# OLED.net
KiCad netlist of a schematic drawn in Altium Designer
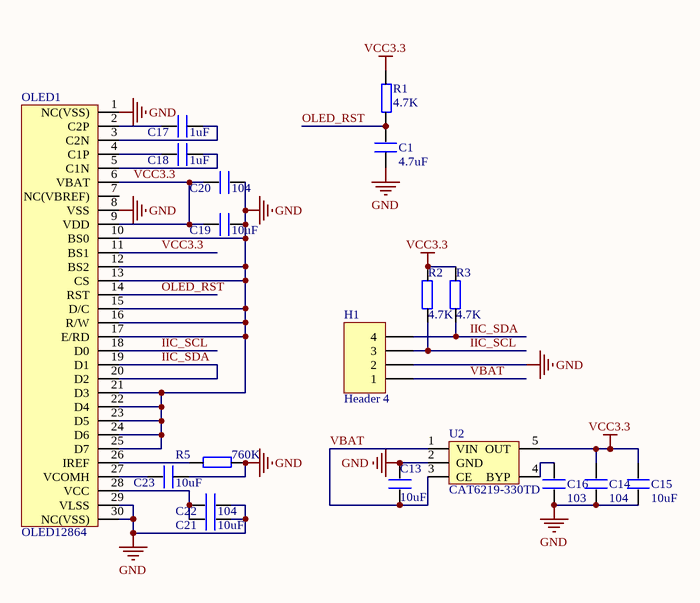
[diagram p0: OLED.SchDoc]

(export (version "E")
  (design (tool "Eeschema 10.0.6"))
  (components
    (comp (ref "C1")
      (value "4.7uF")
      (footprint "C 0603_M")
      (libsource (lib "WarShip V3 STM32103封装库") (part "C"))
    )
    (comp (ref "C13")
      (value "10uF")
      (footprint "C 0603_M")
      (libsource (lib "WarShip V3 STM32103封装库") (part "C"))
    )
    (comp (ref "C14")
      (value "104")
      (footprint "C 0603_M")
      (libsource (lib "WarShip V3 STM32103封装库") (part "C"))
    )
    (comp (ref "C15")
      (value "10uF")
      (footprint "C 0603_M")
      (libsource (lib "WarShip V3 STM32103封装库") (part "C"))
    )
    (comp (ref "C16")
      (value "103")
      (footprint "C 0603_M")
      (libsource (lib "WarShip V3 STM32103封装库") (part "C"))
    )
    (comp (ref "C17")
      (value "1uF")
      (footprint "C 0603_M")
      (libsource (lib "WarShip V3 STM32103封装库") (part "C"))
    )
    (comp (ref "C18")
      (value "1uF")
      (footprint "C 0603_M")
      (libsource (lib "WarShip V3 STM32103封装库") (part "C"))
    )
    (comp (ref "C19")
      (value "10uF")
      (footprint "C 0603_M")
      (libsource (lib "WarShip V3 STM32103封装库") (part "C"))
    )
    (comp (ref "C20")
      (value "104")
      (footprint "C 0603_M")
      (libsource (lib "WarShip V3 STM32103封装库") (part "C"))
    )
    (comp (ref "C21")
      (value "10uF")
      (footprint "C 0603_M")
      (libsource (lib "WarShip V3 STM32103封装库") (part "C"))
    )
    (comp (ref "C22")
      (value "104")
      (footprint "C 0603_M")
      (libsource (lib "WarShip V3 STM32103封装库") (part "C"))
    )
    (comp (ref "C23")
      (value "10uF")
      (footprint "C 0603_M")
      (libsource (lib "WarShip V3 STM32103封装库") (part "C"))
    )
    (comp (ref "H1")
      (value "Header 4")
      (footprint "HDR2.54-LI-4P")
      (description "Header, 4-Pin")
      (fields (field (name "PUBLISHER") "Altium Limited"))
      (libsource (lib "WarShip V3 STM32103封装库") (part "Header 4"))
    )
    (comp (ref "OLED1")
      (value "OLED12864")
      (footprint "OLED_0.96")
      (libsource (lib "OLED模块封装库") (part "OLED12864"))
    )
    (comp (ref "R1")
      (value "4.7K")
      (footprint "R 0603_M")
      (libsource (lib "WarShip V3 STM32103封装库") (part "R"))
    )
    (comp (ref "R2")
      (value "4.7K")
      (footprint "R 0603_M")
      (libsource (lib "WarShip V3 STM32103封装库") (part "R"))
    )
    (comp (ref "R3")
      (value "4.7K")
      (footprint "R 0603_M")
      (libsource (lib "WarShip V3 STM32103封装库") (part "R"))
    )
    (comp (ref "R5")
      (value "760K")
      (footprint "R 0603_M")
      (libsource (lib "WarShip V3 STM32103封装库") (part "R"))
    )
    (comp (ref "U2")
      (value "CAT6219-330TD")
      (footprint "SOT-23-5")
      (description "3.3V 500mA LDO")
      (libsource (lib "STM32H743核心板封装库") (part "CAT6219-330TD"))
    )
  )
  (nets
    (net (code "1") (name "/IIC_SCL") (class "Default")
      (node (ref "H1") (pin "3") (pinfunction "3_3") (pintype "passive"))
      (node (ref "OLED1") (pin "18") (pinfunction "D0_18") (pintype "passive"))
      (node (ref "R2") (pin "2") (pintype "passive"))
    )
    (net (code "2") (name "/IIC_SDA") (class "Default")
      (node (ref "H1") (pin "4") (pinfunction "4_4") (pintype "passive"))
      (node (ref "OLED1") (pin "19") (pinfunction "D1_19") (pintype "passive"))
      (node (ref "OLED1") (pin "20") (pinfunction "D2_20") (pintype "passive"))
      (node (ref "R3") (pin "2") (pintype "passive"))
    )
    (net (code "3") (name "/OLED_RST") (class "Default")
      (node (ref "C1") (pin "1") (pintype "passive"))
      (node (ref "OLED1") (pin "14") (pinfunction "RST_14") (pintype "passive"))
      (node (ref "R1") (pin "1") (pintype "passive"))
    )
    (net (code "4") (name "/VBAT") (class "Default")
      (node (ref "C13") (pin "1") (pintype "passive"))
      (node (ref "H1") (pin "1") (pinfunction "1_1") (pintype "passive"))
      (node (ref "U2") (pin "1") (pinfunction "VIN_1") (pintype "passive"))
      (node (ref "U2") (pin "3") (pinfunction "CE_3") (pintype "passive"))
    )
    (net (code "5") (name "GND") (class "Default")
      (node (ref "C1") (pin "2") (pintype "passive"))
      (node (ref "C13") (pin "2") (pintype "passive"))
      (node (ref "C14") (pin "1") (pintype "passive"))
      (node (ref "C15") (pin "1") (pintype "passive"))
      (node (ref "C16") (pin "1") (pintype "passive"))
      (node (ref "C19") (pin "1") (pintype "passive"))
      (node (ref "C20") (pin "1") (pintype "passive"))
      (node (ref "C21") (pin "1") (pintype "passive"))
      (node (ref "C22") (pin "1") (pintype "passive"))
      (node (ref "C23") (pin "1") (pintype "passive"))
      (node (ref "H1") (pin "2") (pinfunction "2_2") (pintype "passive"))
      (node (ref "OLED1") (pin "1") (pinfunction "NC(VSS)_1") (pintype "passive"))
      (node (ref "OLED1") (pin "10") (pinfunction "BS0_10") (pintype "passive"))
      (node (ref "OLED1") (pin "12") (pinfunction "BS2_12") (pintype "passive"))
      (node (ref "OLED1") (pin "13") (pinfunction "CS_13") (pintype "passive"))
      (node (ref "OLED1") (pin "15") (pinfunction "D/C_15") (pintype "passive"))
      (node (ref "OLED1") (pin "16") (pinfunction "R/W_16") (pintype "passive"))
      (node (ref "OLED1") (pin "17") (pinfunction "E/RD_17") (pintype "passive"))
      (node (ref "OLED1") (pin "21") (pinfunction "D3_21") (pintype "passive"))
      (node (ref "OLED1") (pin "22") (pinfunction "D4_22") (pintype "passive"))
      (node (ref "OLED1") (pin "23") (pinfunction "D5_23") (pintype "passive"))
      (node (ref "OLED1") (pin "24") (pinfunction "D6_24") (pintype "passive"))
      (node (ref "OLED1") (pin "25") (pinfunction "D7_25") (pintype "passive"))
      (node (ref "OLED1") (pin "29") (pinfunction "VLSS_29") (pintype "passive"))
      (node (ref "OLED1") (pin "30") (pinfunction "NC(VSS)_30") (pintype "passive"))
      (node (ref "OLED1") (pin "8") (pinfunction "VSS_8") (pintype "passive"))
      (node (ref "R5") (pin "1") (pintype "passive"))
      (node (ref "U2") (pin "2") (pinfunction "GND_2") (pintype "passive"))
    )
    (net (code "6") (name "Net-(OLED1-C1N)") (class "Default")
      (node (ref "C18") (pin "1") (pintype "passive"))
      (node (ref "OLED1") (pin "5") (pinfunction "C1N_5") (pintype "passive"))
    )
    (net (code "7") (name "Net-(OLED1-C1P)") (class "Default")
      (node (ref "C18") (pin "2") (pintype "passive"))
      (node (ref "OLED1") (pin "4") (pinfunction "C1P_4") (pintype "passive"))
    )
    (net (code "8") (name "Net-(OLED1-C2N)") (class "Default")
      (node (ref "C17") (pin "1") (pintype "passive"))
      (node (ref "OLED1") (pin "3") (pinfunction "C2N_3") (pintype "passive"))
    )
    (net (code "9") (name "Net-(OLED1-C2P)") (class "Default")
      (node (ref "C17") (pin "2") (pintype "passive"))
      (node (ref "OLED1") (pin "2") (pinfunction "C2P_2") (pintype "passive"))
    )
    (net (code "10") (name "Net-(OLED1-IREF)") (class "Default")
      (node (ref "OLED1") (pin "26") (pinfunction "IREF_26") (pintype "passive"))
      (node (ref "R5") (pin "2") (pintype "passive"))
    )
    (net (code "11") (name "Net-(OLED1-VCC)") (class "Default")
      (node (ref "C21") (pin "2") (pintype "passive"))
      (node (ref "C22") (pin "2") (pintype "passive"))
      (node (ref "OLED1") (pin "28") (pinfunction "VCC_28") (pintype "passive"))
    )
    (net (code "12") (name "Net-(OLED1-VCOMH)") (class "Default")
      (node (ref "C23") (pin "2") (pintype "passive"))
      (node (ref "OLED1") (pin "27") (pinfunction "VCOMH_27") (pintype "passive"))
    )
    (net (code "13") (name "Net-(U2-BYP)") (class "Default")
      (node (ref "C16") (pin "2") (pintype "passive"))
      (node (ref "U2") (pin "4") (pinfunction "BYP_4") (pintype "passive"))
    )
    (net (code "14") (name "VCC3.3") (class "Default")
      (node (ref "C14") (pin "2") (pintype "passive"))
      (node (ref "C15") (pin "2") (pintype "passive"))
      (node (ref "C19") (pin "2") (pintype "passive"))
      (node (ref "C20") (pin "2") (pintype "passive"))
      (node (ref "OLED1") (pin "11") (pinfunction "BS1_11") (pintype "passive"))
      (node (ref "OLED1") (pin "6") (pinfunction "VBAT_6") (pintype "passive"))
      (node (ref "OLED1") (pin "9") (pinfunction "VDD_9") (pintype "passive"))
      (node (ref "R1") (pin "2") (pintype "passive"))
      (node (ref "R2") (pin "1") (pintype "passive"))
      (node (ref "R3") (pin "1") (pintype "passive"))
      (node (ref "U2") (pin "5") (pinfunction "OUT_5") (pintype "passive"))
    )
    (net (code "15") (name "unconnected-(OLED1-NC(VBREF)-Pad7)") (class "Default")
      (node (ref "OLED1") (pin "7") (pinfunction "NC(VBREF)_7") (pintype "passive"))
    )
  )
)
